# Programming_Circuit.net
KiCad netlist of a schematic drawn in Altium Designer
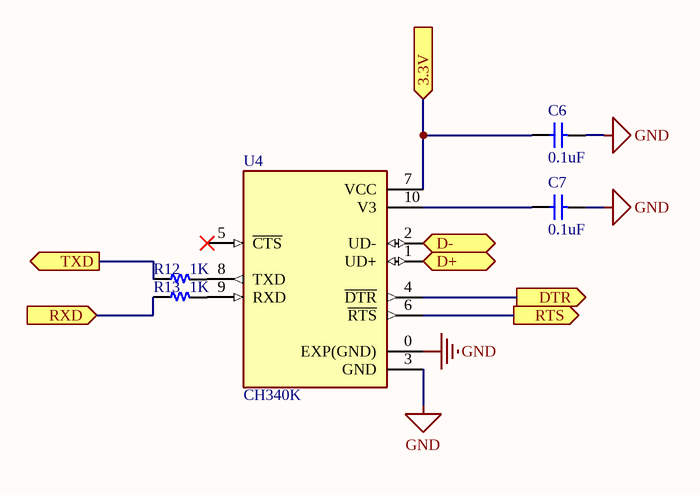
[diagram p0: Programming Circuit.SchDoc]

(export (version "E")
  (design (tool "Eeschema 10.0.6"))
  (components
    (comp (ref "C6")
      (value "0.1uF")
      (footprint "C 0805")
      (description "Capacitor non-pol")
      (libsource (lib "chipfc_libs") (part "Capacitor NP"))
    )
    (comp (ref "C7")
      (value "0.1uF")
      (footprint "C 0805")
      (description "Capacitor non-pol")
      (libsource (lib "chipfc_libs") (part "Capacitor NP"))
    )
    (comp (ref "R12")
      (value "1K")
      (footprint "R 0805")
      (description "Resistor")
      (libsource (lib "chipfc_libs") (part "Resistor"))
    )
    (comp (ref "R13")
      (value "1K")
      (footprint "R 0805")
      (description "Resistor")
      (libsource (lib "chipfc_libs") (part "Resistor"))
    )
    (comp (ref "U4")
      (value "CH340K")
      (footprint "SOP100P600X160-11N")
      (description "USB to Serial Port Chip")
      (fields (field (name "MF") "WCH"))
      (libsource (lib "CH340K") (part "CH340K"))
    )
  )
  (nets
    (net (code "1") (name "/3.3V") (class "Default")
      (node (ref "C6") (pin "2") (pinfunction "2_2") (pintype "passive"))
      (node (ref "U4") (pin "7") (pinfunction "VCC_7") (pintype "power_in"))
    )
    (net (code "2") (name "/D+") (class "Default")
      (node (ref "U4") (pin "1") (pinfunction "UD+_1") (pintype "bidirectional"))
    )
    (net (code "3") (name "/D-") (class "Default")
      (node (ref "U4") (pin "2") (pinfunction "UD-_2") (pintype "bidirectional"))
    )
    (net (code "4") (name "/DTR") (class "Default")
      (node (ref "U4") (pin "4") (pinfunction "~{DTR}_4") (pintype "output"))
    )
    (net (code "5") (name "/RTS") (class "Default")
      (node (ref "U4") (pin "6") (pinfunction "~{RTS}_6") (pintype "output"))
    )
    (net (code "6") (name "/RXD") (class "Default")
      (node (ref "R13") (pin "1") (pinfunction "1_1") (pintype "passive"))
    )
    (net (code "7") (name "/TXD") (class "Default")
      (node (ref "R12") (pin "1") (pinfunction "1_1") (pintype "passive"))
    )
    (net (code "8") (name "GND") (class "Default")
      (node (ref "C6") (pin "1") (pinfunction "1_1") (pintype "passive"))
      (node (ref "C7") (pin "1") (pinfunction "1_1") (pintype "passive"))
      (node (ref "U4") (pin "0") (pinfunction "EXP(GND)_0") (pintype "power_in"))
      (node (ref "U4") (pin "3") (pinfunction "GND_3") (pintype "power_in"))
    )
    (net (code "9") (name "Net-(U4-RXD)") (class "Default")
      (node (ref "R13") (pin "2") (pinfunction "2_2") (pintype "passive"))
      (node (ref "U4") (pin "9") (pinfunction "RXD_9") (pintype "input"))
    )
    (net (code "10") (name "Net-(U4-TXD)") (class "Default")
      (node (ref "R12") (pin "2") (pinfunction "2_2") (pintype "passive"))
      (node (ref "U4") (pin "8") (pinfunction "TXD_8") (pintype "output"))
    )
    (net (code "11") (name "Net-(U4-V3)") (class "Default")
      (node (ref "C7") (pin "2") (pinfunction "2_2") (pintype "passive"))
      (node (ref "U4") (pin "10") (pinfunction "V3_10") (pintype "power_in"))
    )
    (net (code "12") (name "unconnected-(U4-~{CTS}-Pad5)") (class "Default")
      (node (ref "U4") (pin "5") (pinfunction "~{CTS}_5") (pintype "input+no_connect"))
    )
  )
)
